# indicator.net
KiCad netlist of a schematic drawn in Altium Designer
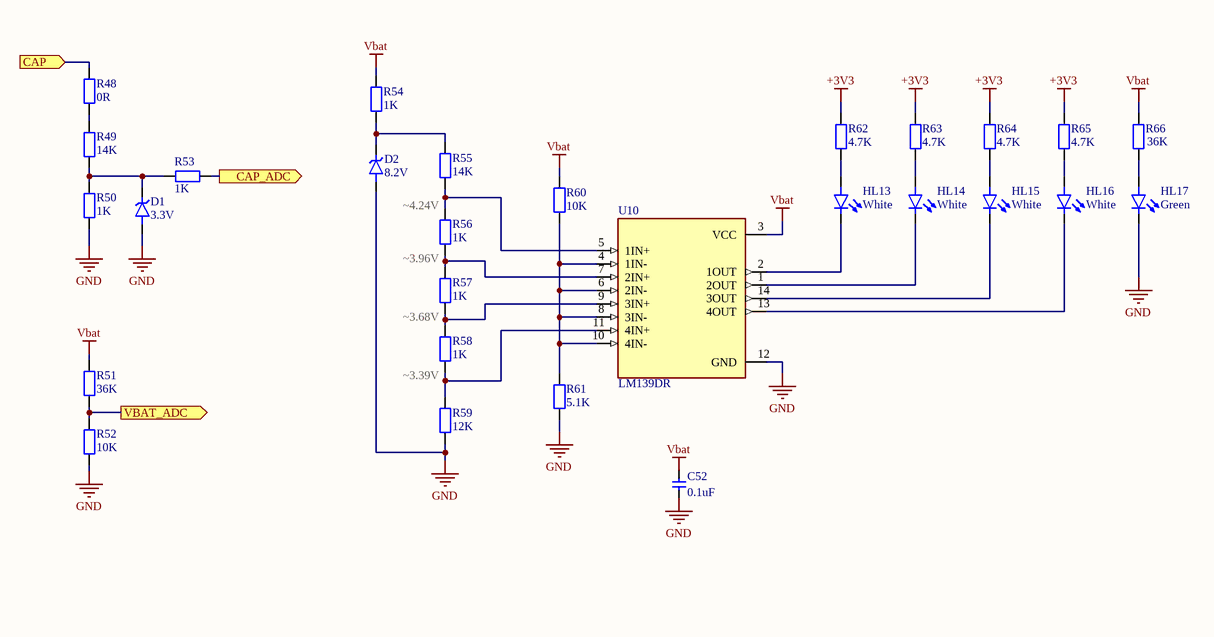
[diagram p0: indicator.SchDoc]

(export (version "E")
  (design (tool "Eeschema 10.0.6"))
  (components
    (comp (ref "C52")
      (value "0.1uF")
      (footprint "CAP0805")
      (description "Ceramic SMD Cap")
      (libsource (lib "Asterisk") (part "CAP Ceramic"))
    )
    (comp (ref "D1")
      (value "3.3V")
      (footprint "SOD-80")
      (description "BZV55C3V3")
      (libsource (lib "Asterisk") (part "Diode Zener"))
    )
    (comp (ref "D2")
      (value "8.2V")
      (footprint "SOD-80")
      (description "BZV55C8V2")
      (libsource (lib "Asterisk") (part "Diode Zener"))
    )
    (comp (ref "HL13")
      (value "White")
      (footprint "LED0603_GREEN")
      (description "LED smd")
      (libsource (lib "Asterisk") (part "LED"))
    )
    (comp (ref "HL14")
      (value "White")
      (footprint "LED0603_GREEN")
      (description "LED smd")
      (libsource (lib "Asterisk") (part "LED"))
    )
    (comp (ref "HL15")
      (value "White")
      (footprint "LED0603_GREEN")
      (description "LED smd")
      (libsource (lib "Asterisk") (part "LED"))
    )
    (comp (ref "HL16")
      (value "White")
      (footprint "LED0603_GREEN")
      (description "LED smd")
      (libsource (lib "Asterisk") (part "LED"))
    )
    (comp (ref "HL17")
      (value "Green")
      (footprint "LED0603_GREEN")
      (description "LED smd")
      (libsource (lib "Asterisk") (part "LED"))
    )
    (comp (ref "R48")
      (value "0R")
      (footprint "RES0805")
      (description "RES smd")
      (libsource (lib "Asterisk") (part "RES"))
    )
    (comp (ref "R49")
      (value "14K")
      (footprint "RES0805")
      (description "RES smd")
      (libsource (lib "Asterisk") (part "RES"))
    )
    (comp (ref "R50")
      (value "1K")
      (footprint "RES0805")
      (description "RES smd")
      (libsource (lib "Asterisk") (part "RES"))
    )
    (comp (ref "R51")
      (value "36K")
      (footprint "RES0805")
      (description "RES smd")
      (libsource (lib "Asterisk") (part "RES"))
    )
    (comp (ref "R52")
      (value "10K")
      (footprint "RES0805")
      (description "RES smd")
      (libsource (lib "Asterisk") (part "RES"))
    )
    (comp (ref "R53")
      (value "1K")
      (footprint "RES0805")
      (description "RES smd")
      (libsource (lib "Asterisk") (part "RES"))
    )
    (comp (ref "R54")
      (value "1K")
      (footprint "RES0805")
      (description "RES smd")
      (libsource (lib "Asterisk") (part "RES"))
    )
    (comp (ref "R55")
      (value "14K")
      (footprint "RES0805")
      (description "RES smd")
      (libsource (lib "Asterisk") (part "RES"))
    )
    (comp (ref "R56")
      (value "1K")
      (footprint "RES0805")
      (description "RES smd")
      (libsource (lib "Asterisk") (part "RES"))
    )
    (comp (ref "R57")
      (value "1K")
      (footprint "RES0805")
      (description "RES smd")
      (libsource (lib "Asterisk") (part "RES"))
    )
    (comp (ref "R58")
      (value "1K")
      (footprint "RES0805")
      (description "RES smd")
      (libsource (lib "Asterisk") (part "RES"))
    )
    (comp (ref "R59")
      (value "12K")
      (footprint "RES0805")
      (description "RES smd")
      (libsource (lib "Asterisk") (part "RES"))
    )
    (comp (ref "R60")
      (value "10K")
      (footprint "RES0805")
      (description "RES smd")
      (libsource (lib "Asterisk") (part "RES"))
    )
    (comp (ref "R61")
      (value "5.1K")
      (footprint "RES0805")
      (description "RES smd")
      (libsource (lib "Asterisk") (part "RES"))
    )
    (comp (ref "R62")
      (value "4.7K")
      (footprint "RES0805")
      (description "RES smd")
      (libsource (lib "Asterisk") (part "RES"))
    )
    (comp (ref "R63")
      (value "4.7K")
      (footprint "RES0805")
      (description "RES smd")
      (libsource (lib "Asterisk") (part "RES"))
    )
    (comp (ref "R64")
      (value "4.7K")
      (footprint "RES0805")
      (description "RES smd")
      (libsource (lib "Asterisk") (part "RES"))
    )
    (comp (ref "R65")
      (value "4.7K")
      (footprint "RES0805")
      (description "RES smd")
      (libsource (lib "Asterisk") (part "RES"))
    )
    (comp (ref "R66")
      (value "36K")
      (footprint "RES0805")
      (description "RES smd")
      (libsource (lib "Asterisk") (part "RES"))
    )
    (comp (ref "U10")
      (value "LM139DR")
      (footprint "SOIC-14")
      (description "Quad differential comparator")
      (libsource (lib "Asterisk") (part "LM139DR"))
    )
  )
  (nets
    (net (code "1") (name "+3V3") (class "Default")
      (node (ref "R62") (pin "2") (pinfunction "2_2") (pintype "passive"))
      (node (ref "R63") (pin "2") (pinfunction "2_2") (pintype "passive"))
      (node (ref "R64") (pin "2") (pinfunction "2_2") (pintype "passive"))
      (node (ref "R65") (pin "2") (pinfunction "2_2") (pintype "passive"))
    )
    (net (code "2") (name "/CAP") (class "Default")
      (node (ref "R48") (pin "2") (pinfunction "2_2") (pintype "passive"))
    )
    (net (code "3") (name "/CAP_ADC") (class "Default")
      (node (ref "R53") (pin "1") (pinfunction "1_1") (pintype "passive"))
    )
    (net (code "4") (name "/VBAT_ADC") (class "Default")
      (node (ref "R51") (pin "1") (pinfunction "1_1") (pintype "passive"))
      (node (ref "R52") (pin "2") (pinfunction "2_2") (pintype "passive"))
    )
    (net (code "5") (name "GND") (class "Default")
      (node (ref "C52") (pin "1") (pinfunction "1_1") (pintype "passive"))
      (node (ref "D1") (pin "A") (pinfunction "A_A") (pintype "passive"))
      (node (ref "D2") (pin "A") (pinfunction "A_A") (pintype "passive"))
      (node (ref "HL17") (pin "1") (pinfunction "K_1") (pintype "passive"))
      (node (ref "R50") (pin "1") (pinfunction "1_1") (pintype "passive"))
      (node (ref "R52") (pin "1") (pinfunction "1_1") (pintype "passive"))
      (node (ref "R59") (pin "1") (pinfunction "1_1") (pintype "passive"))
      (node (ref "R61") (pin "1") (pinfunction "1_1") (pintype "passive"))
      (node (ref "U10") (pin "12") (pinfunction "GND_12") (pintype "power_in"))
    )
    (net (code "6") (name "Net-(D1-PadK)") (class "Default")
      (node (ref "D1") (pin "K") (pinfunction "K_K") (pintype "passive"))
      (node (ref "R49") (pin "1") (pinfunction "1_1") (pintype "passive"))
      (node (ref "R50") (pin "2") (pinfunction "2_2") (pintype "passive"))
      (node (ref "R53") (pin "2") (pinfunction "2_2") (pintype "passive"))
    )
    (net (code "7") (name "Net-(D2-PadK)") (class "Default")
      (node (ref "D2") (pin "K") (pinfunction "K_K") (pintype "passive"))
      (node (ref "R54") (pin "1") (pinfunction "1_1") (pintype "passive"))
      (node (ref "R55") (pin "2") (pinfunction "2_2") (pintype "passive"))
    )
    (net (code "8") (name "Net-(HL13-A)") (class "Default")
      (node (ref "HL13") (pin "2") (pinfunction "A_2") (pintype "passive"))
      (node (ref "R62") (pin "1") (pinfunction "1_1") (pintype "passive"))
    )
    (net (code "9") (name "Net-(HL13-K)") (class "Default")
      (node (ref "HL13") (pin "1") (pinfunction "K_1") (pintype "passive"))
      (node (ref "U10") (pin "2") (pinfunction "1OUT_2") (pintype "output"))
    )
    (net (code "10") (name "Net-(HL14-A)") (class "Default")
      (node (ref "HL14") (pin "2") (pinfunction "A_2") (pintype "passive"))
      (node (ref "R63") (pin "1") (pinfunction "1_1") (pintype "passive"))
    )
    (net (code "11") (name "Net-(HL14-K)") (class "Default")
      (node (ref "HL14") (pin "1") (pinfunction "K_1") (pintype "passive"))
      (node (ref "U10") (pin "1") (pinfunction "2OUT_1") (pintype "output"))
    )
    (net (code "12") (name "Net-(HL15-A)") (class "Default")
      (node (ref "HL15") (pin "2") (pinfunction "A_2") (pintype "passive"))
      (node (ref "R64") (pin "1") (pinfunction "1_1") (pintype "passive"))
    )
    (net (code "13") (name "Net-(HL15-K)") (class "Default")
      (node (ref "HL15") (pin "1") (pinfunction "K_1") (pintype "passive"))
      (node (ref "U10") (pin "14") (pinfunction "3OUT_14") (pintype "output"))
    )
    (net (code "14") (name "Net-(HL16-A)") (class "Default")
      (node (ref "HL16") (pin "2") (pinfunction "A_2") (pintype "passive"))
      (node (ref "R65") (pin "1") (pinfunction "1_1") (pintype "passive"))
    )
    (net (code "15") (name "Net-(HL16-K)") (class "Default")
      (node (ref "HL16") (pin "1") (pinfunction "K_1") (pintype "passive"))
      (node (ref "U10") (pin "13") (pinfunction "4OUT_13") (pintype "output"))
    )
    (net (code "16") (name "Net-(HL17-A)") (class "Default")
      (node (ref "HL17") (pin "2") (pinfunction "A_2") (pintype "passive"))
      (node (ref "R66") (pin "1") (pinfunction "1_1") (pintype "passive"))
    )
    (net (code "17") (name "Net-(R48-Pad1)") (class "Default")
      (node (ref "R48") (pin "1") (pinfunction "1_1") (pintype "passive"))
      (node (ref "R49") (pin "2") (pinfunction "2_2") (pintype "passive"))
    )
    (net (code "18") (name "Net-(U10-1IN+)") (class "Default")
      (node (ref "R55") (pin "1") (pinfunction "1_1") (pintype "passive"))
      (node (ref "R56") (pin "2") (pinfunction "2_2") (pintype "passive"))
      (node (ref "U10") (pin "5") (pinfunction "1IN+_5") (pintype "input"))
    )
    (net (code "19") (name "Net-(U10-1IN-)") (class "Default")
      (node (ref "R60") (pin "1") (pinfunction "1_1") (pintype "passive"))
      (node (ref "R61") (pin "2") (pinfunction "2_2") (pintype "passive"))
      (node (ref "U10") (pin "10") (pinfunction "4IN-_10") (pintype "input"))
      (node (ref "U10") (pin "4") (pinfunction "1IN-_4") (pintype "input"))
      (node (ref "U10") (pin "6") (pinfunction "2IN-_6") (pintype "input"))
      (node (ref "U10") (pin "8") (pinfunction "3IN-_8") (pintype "input"))
    )
    (net (code "20") (name "Net-(U10-2IN+)") (class "Default")
      (node (ref "R56") (pin "1") (pinfunction "1_1") (pintype "passive"))
      (node (ref "R57") (pin "2") (pinfunction "2_2") (pintype "passive"))
      (node (ref "U10") (pin "7") (pinfunction "2IN+_7") (pintype "input"))
    )
    (net (code "21") (name "Net-(U10-3IN+)") (class "Default")
      (node (ref "R57") (pin "1") (pinfunction "1_1") (pintype "passive"))
      (node (ref "R58") (pin "2") (pinfunction "2_2") (pintype "passive"))
      (node (ref "U10") (pin "9") (pinfunction "3IN+_9") (pintype "input"))
    )
    (net (code "22") (name "Net-(U10-4IN+)") (class "Default")
      (node (ref "R58") (pin "1") (pinfunction "1_1") (pintype "passive"))
      (node (ref "R59") (pin "2") (pinfunction "2_2") (pintype "passive"))
      (node (ref "U10") (pin "11") (pinfunction "4IN+_11") (pintype "input"))
    )
    (net (code "23") (name "Vbat") (class "Default")
      (node (ref "C52") (pin "2") (pinfunction "2_2") (pintype "passive"))
      (node (ref "R51") (pin "2") (pinfunction "2_2") (pintype "passive"))
      (node (ref "R54") (pin "2") (pinfunction "2_2") (pintype "passive"))
      (node (ref "R60") (pin "2") (pinfunction "2_2") (pintype "passive"))
      (node (ref "R66") (pin "2") (pinfunction "2_2") (pintype "passive"))
      (node (ref "U10") (pin "3") (pinfunction "VCC_3") (pintype "power_in"))
    )
  )
)
